# Sheet_C1.net
KiCad netlist of a schematic drawn in Altium Designer
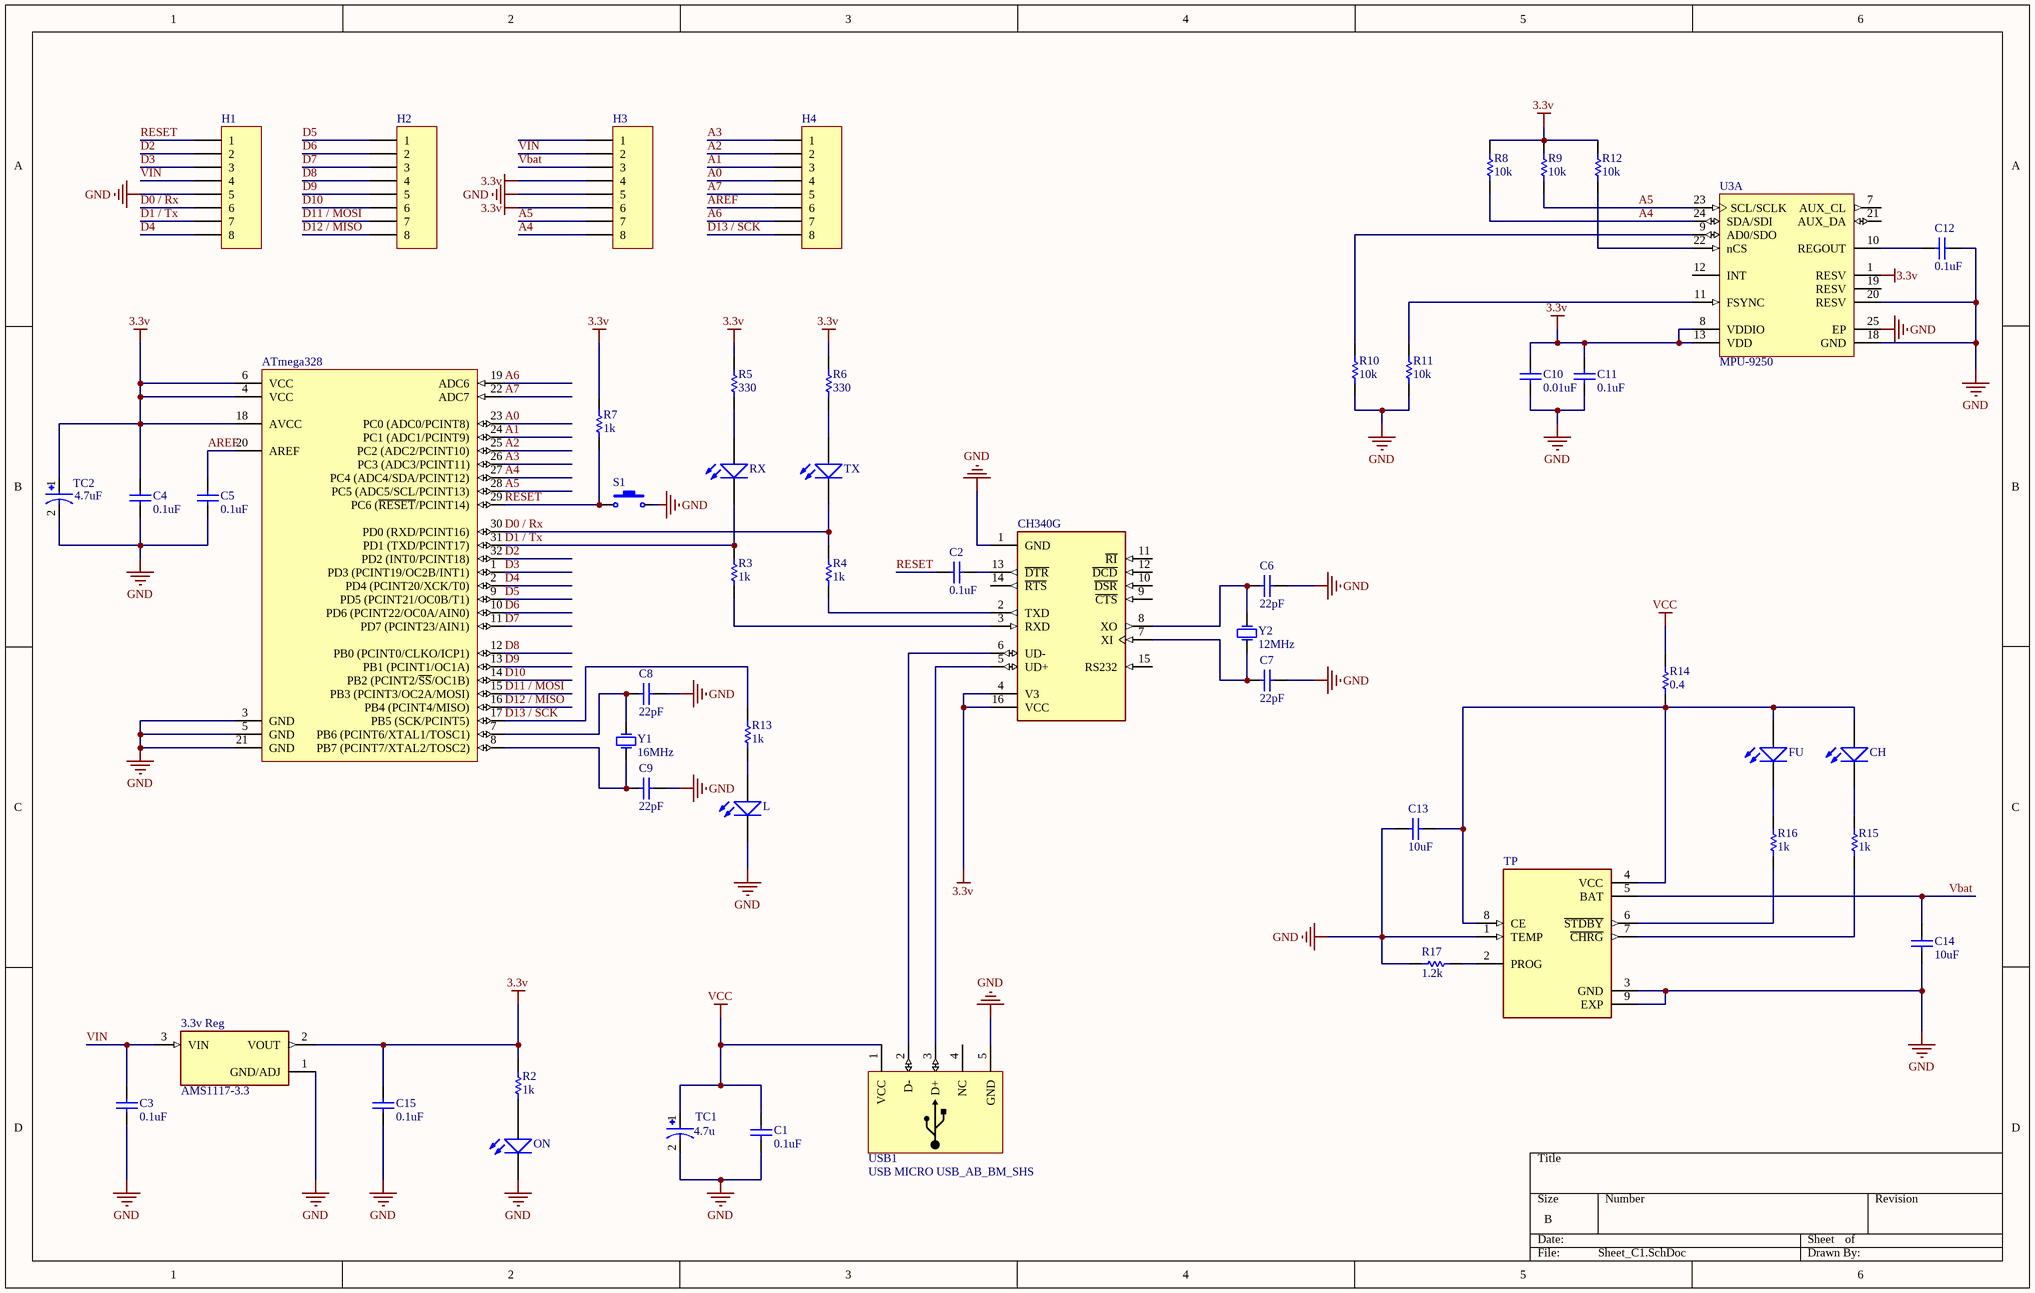
[diagram p0: Sheet_C1.SchDoc]

(export (version "E")
  (design (tool "Eeschema 10.0.6"))
  (components
    (comp (ref "3.3v Reg")
      (value "AMS1117-3.3")
      (footprint "SOT229P700X180-4N")
      (description "Sot223/Pkg 1-Amp 3.3-Volt Low Drop Out Voltage Regulatator")
      (fields (field (name "MF") "Advanced Monolithic Systems"))
      (libsource (lib "AMS1117-3.3") (part "AMS1117-3.3"))
    )
    (comp (ref "ATmega328")
      (value "~")
      (footprint "32A_L")
      (libsource (lib "Altium Content Vault") (part "MC-8B-ATM48-SQ32"))
    )
    (comp (ref "C1")
      (value "0.1uF")
      (footprint "CAP0805")
      (description "CAP0805")
      (libsource (lib "CAP0805") (part "CAP0805"))
    )
    (comp (ref "C2")
      (value "0.1uF")
      (footprint "CAP0805")
      (description "CAP0805")
      (libsource (lib "CAP0805") (part "CAP0805"))
    )
    (comp (ref "C3")
      (value "0.1uF")
      (footprint "CAP0805")
      (description "CAP0805")
      (libsource (lib "CAP0805") (part "CAP0805"))
    )
    (comp (ref "C4")
      (value "0.1uF")
      (footprint "CAP0805")
      (description "CAP0805")
      (libsource (lib "CAP0805") (part "CAP0805"))
    )
    (comp (ref "C5")
      (value "0.1uF")
      (footprint "CAP0805")
      (description "CAP0805")
      (libsource (lib "CAP0805") (part "CAP0805"))
    )
    (comp (ref "C6")
      (value "22pF")
      (footprint "CAP0805")
      (description "CAP0805")
      (libsource (lib "CAP0805") (part "CAP0805"))
    )
    (comp (ref "C7")
      (value "22pF")
      (footprint "CAP0805")
      (description "CAP0805")
      (libsource (lib "CAP0805") (part "CAP0805"))
    )
    (comp (ref "C8")
      (value "22pF")
      (footprint "CAP0805")
      (description "CAP0805")
      (libsource (lib "CAP0805") (part "CAP0805"))
    )
    (comp (ref "C9")
      (value "22pF")
      (footprint "CAP0805")
      (description "CAP0805")
      (libsource (lib "CAP0805") (part "CAP0805"))
    )
    (comp (ref "C10")
      (value "0.01uF")
      (footprint "CAP0805")
      (description "CAP0805")
      (libsource (lib "CAP0805") (part "CAP0805"))
    )
    (comp (ref "C11")
      (value "0.1uF")
      (footprint "CAP0805")
      (description "CAP0805")
      (libsource (lib "CAP0805") (part "CAP0805"))
    )
    (comp (ref "C12")
      (value "0.1uF")
      (footprint "CAP0805")
      (description "CAP0805")
      (libsource (lib "CAP0805") (part "CAP0805"))
    )
    (comp (ref "C13")
      (value "10uF")
      (footprint "CAP0805")
      (description "CAP0805")
      (libsource (lib "CAP0805") (part "CAP0805"))
    )
    (comp (ref "C14")
      (value "10uF")
      (footprint "CAP0805")
      (description "CAP0805")
      (libsource (lib "CAP0805") (part "CAP0805"))
    )
    (comp (ref "C15")
      (value "0.1uF")
      (footprint "CAP0805")
      (description "CAP0805")
      (libsource (lib "CAP0805") (part "CAP0805"))
    )
    (comp (ref "CH")
      (value "~")
      (footprint "LED_SMD_0805")
      (libsource (lib "LED_SMD_0805") (part "LED_SMD_0805"))
    )
    (comp (ref "CH340G")
      (value "~")
      (footprint "SOIC127P600X180-16N")
      (description "USB Interface Integrated Circuit")
      (fields (field (name "MP") "Ch340G") (field (name "MF") "WCH"))
      (libsource (lib "CH340G") (part "CH340G"))
    )
    (comp (ref "FU")
      (value "~")
      (footprint "LED_SMD_0805")
      (libsource (lib "LED_SMD_0805") (part "LED_SMD_0805"))
    )
    (comp (ref "H1") (value "~") (footprint "Header 8") (libsource (lib "Header 8") (part "Header 8")))
    (comp (ref "H2") (value "~") (footprint "Header 8") (libsource (lib "Header 8") (part "Header 8")))
    (comp (ref "H3") (value "~") (footprint "Header 8") (libsource (lib "Header 8") (part "Header 8")))
    (comp (ref "H4") (value "~") (footprint "Header 8") (libsource (lib "Header 8") (part "Header 8")))
    (comp (ref "L")
      (value "~")
      (footprint "LED_SMD_0805")
      (libsource (lib "LED_SMD_0805") (part "LED_SMD_0805"))
    )
    (comp (ref "ON")
      (value "~")
      (footprint "LED_SMD_0805")
      (libsource (lib "LED_SMD_0805") (part "LED_SMD_0805"))
    )
    (comp (ref "R2")
      (value "1k")
      (footprint "RES0805")
      (description "RES0805")
      (libsource (lib "RES0805") (part "RES0805"))
    )
    (comp (ref "R3")
      (value "1k")
      (footprint "RES0805")
      (description "RES0805")
      (libsource (lib "RES0805") (part "RES0805"))
    )
    (comp (ref "R4")
      (value "1k")
      (footprint "RES0805")
      (description "RES0805")
      (libsource (lib "RES0805") (part "RES0805"))
    )
    (comp (ref "R5")
      (value "330")
      (footprint "RES0805")
      (description "RES0805")
      (libsource (lib "RES0805") (part "RES0805"))
    )
    (comp (ref "R6")
      (value "330")
      (footprint "RES0805")
      (description "RES0805")
      (libsource (lib "RES0805") (part "RES0805"))
    )
    (comp (ref "R7")
      (value "1k")
      (footprint "RES0805")
      (description "RES0805")
      (libsource (lib "RES0805") (part "RES0805"))
    )
    (comp (ref "R8")
      (value "10k")
      (footprint "RES0805")
      (description "RES0805")
      (libsource (lib "RES0805") (part "RES0805"))
    )
    (comp (ref "R9")
      (value "10k")
      (footprint "RES0805")
      (description "RES0805")
      (libsource (lib "RES0805") (part "RES0805"))
    )
    (comp (ref "R10")
      (value "10k")
      (footprint "RES0805")
      (description "RES0805")
      (libsource (lib "RES0805") (part "RES0805"))
    )
    (comp (ref "R11")
      (value "10k")
      (footprint "RES0805")
      (description "RES0805")
      (libsource (lib "RES0805") (part "RES0805"))
    )
    (comp (ref "R12")
      (value "10k")
      (footprint "RES0805")
      (description "RES0805")
      (libsource (lib "RES0805") (part "RES0805"))
    )
    (comp (ref "R13")
      (value "1k")
      (footprint "RES0805")
      (description "RES0805")
      (libsource (lib "RES0805") (part "RES0805"))
    )
    (comp (ref "R14")
      (value "0.4")
      (footprint "RES0805")
      (description "RES0805")
      (libsource (lib "RES0805") (part "RES0805"))
    )
    (comp (ref "R15")
      (value "1k")
      (footprint "RES0805")
      (description "RES0805")
      (libsource (lib "RES0805") (part "RES0805"))
    )
    (comp (ref "R16")
      (value "1k")
      (footprint "RES0805")
      (description "RES0805")
      (libsource (lib "RES0805") (part "RES0805"))
    )
    (comp (ref "R17")
      (value "1.2k")
      (footprint "RES0805")
      (description "RES0805")
      (libsource (lib "RES0805") (part "RES0805"))
    )
    (comp (ref "RX")
      (value "~")
      (footprint "LED_SMD_0805")
      (libsource (lib "LED_SMD_0805") (part "LED_SMD_0805"))
    )
    (comp (ref "S1")
      (value "~")
      (footprint "Push Button Switch SMD")
      (libsource (lib "Push Button Switch SMD") (part "Push Button Switch SMD"))
    )
    (comp (ref "TC1")
      (value "4.7u")
      (footprint "CAPMP3516X190N")
      (description "4.7 ÂµF Molded Tantalum Capacitors 25 V 1411 (3528 Metric), 1210 1.5Ohm")
      (fields (field (name "MP") "TAJB475K025RNJ") (field (name "MF") "AVX"))
      (libsource (lib "TAJB475K025RNJ") (part "TAJB475K025RNJ"))
    )
    (comp (ref "TC2")
      (value "4.7uF")
      (footprint "CAPMP3516X190N")
      (description "4.7 ÂµF Molded Tantalum Capacitors 25 V 1411 (3528 Metric), 1210 1.5Ohm")
      (fields (field (name "MP") "TAJB475K025RNJ") (field (name "MF") "AVX"))
      (libsource (lib "TAJB475K025RNJ") (part "TAJB475K025RNJ"))
    )
    (comp (ref "TP")
      (value "~")
      (footprint "SOIC127P600X175-9N")
      (description "TP4056-42-ESOP8 TP")
      (fields (field (name "MF") "Lite-On Semiconductor") (field (name "MP") "TP4056-42-ESOP8"))
      (libsource (lib "TP4056-42-ESOP8") (part "TP4056-42-ESOP8"))
    )
    (comp (ref "TX")
      (value "~")
      (footprint "LED_SMD_0805")
      (libsource (lib "LED_SMD_0805") (part "LED_SMD_0805"))
    )
    (comp (ref "U3")
      (value "MPU-9250")
      (footprint "INSE-QFN-24-1700X1540TP_M")
      (description "9-axis MotionTracking device, 2.4 to 3,6 V, -40 to 85 degC, 24-Pin QFN, RoHS, Tape and Reel")
      (fields (field (name "MANUFACTURER") "InvenSense"))
      (libsource (lib "Altium Content Vault") (part "INSE-MPU-9250-QFN-24"))
    )
    (comp (ref "USB1")
      (value "USB MICRO USB_AB_BM_SHS")
      (footprint "USB MICRO USB_AB_BM_SHS")
      (libsource (lib "USB MICRO USB_AB_BM_SHS") (part "USB MICRO USB_AB_BM_SHS"))
    )
    (comp (ref "Y1")
      (value "16MHz")
      (footprint "Crystal SMD")
      (description "Crystal SMD")
      (libsource (lib "Crystal SMD") (part "Crystal SMD"))
    )
    (comp (ref "Y2")
      (value "12MHz")
      (footprint "Crystal SMD")
      (description "Crystal SMD")
      (libsource (lib "Crystal SMD") (part "Crystal SMD"))
    )
  )
  (nets
    (net (code "1") (name "/A0") (class "Default")
      (node (ref "ATmega328") (pin "23") (pinfunction "PC0_(ADC0/PCINT8)_23") (pintype "bidirectional"))
      (node (ref "H4") (pin "4") (pinfunction "4_4") (pintype "passive"))
    )
    (net (code "2") (name "/A1") (class "Default")
      (node (ref "ATmega328") (pin "24") (pinfunction "PC1_(ADC1/PCINT9)_24") (pintype "bidirectional"))
      (node (ref "H4") (pin "3") (pinfunction "3_3") (pintype "passive"))
    )
    (net (code "3") (name "/A2") (class "Default")
      (node (ref "ATmega328") (pin "25") (pinfunction "PC2_(ADC2/PCINT10)_25") (pintype "bidirectional"))
      (node (ref "H4") (pin "2") (pinfunction "2_2") (pintype "passive"))
    )
    (net (code "4") (name "/A3") (class "Default")
      (node (ref "ATmega328") (pin "26") (pinfunction "PC3_(ADC3/PCINT11)_26") (pintype "bidirectional"))
      (node (ref "H4") (pin "1") (pinfunction "1_1") (pintype "passive"))
    )
    (net (code "5") (name "/A4") (class "Default")
      (node (ref "ATmega328") (pin "27") (pinfunction "PC4_(ADC4/SDA/PCINT12)_27") (pintype "bidirectional"))
      (node (ref "H3") (pin "8") (pinfunction "8_8") (pintype "passive"))
      (node (ref "R8") (pin "1") (pinfunction "1_1") (pintype "passive"))
      (node (ref "U3") (pin "24") (pinfunction "SDA/SDI_24") (pintype "bidirectional"))
    )
    (net (code "6") (name "/A5") (class "Default")
      (node (ref "ATmega328") (pin "28") (pinfunction "PC5_(ADC5/SCL/PCINT13)_28") (pintype "bidirectional"))
      (node (ref "H3") (pin "7") (pinfunction "7_7") (pintype "passive"))
      (node (ref "R9") (pin "1") (pinfunction "1_1") (pintype "passive"))
      (node (ref "U3") (pin "23") (pinfunction "SCL/SCLK_23") (pintype "input"))
    )
    (net (code "7") (name "/A6") (class "Default")
      (node (ref "ATmega328") (pin "19") (pinfunction "ADC6_19") (pintype "input"))
      (node (ref "H4") (pin "7") (pinfunction "7_7") (pintype "passive"))
    )
    (net (code "8") (name "/A7") (class "Default")
      (node (ref "ATmega328") (pin "22") (pinfunction "ADC7_22") (pintype "input"))
      (node (ref "H4") (pin "5") (pinfunction "5_5") (pintype "passive"))
    )
    (net (code "9") (name "/AREF") (class "Default")
      (node (ref "ATmega328") (pin "20") (pinfunction "AREF_20") (pintype "passive"))
      (node (ref "C5") (pin "2") (pinfunction "2_2") (pintype "passive"))
      (node (ref "H4") (pin "6") (pinfunction "6_6") (pintype "passive"))
    )
    (net (code "10") (name "/D0 {slash} Rx") (class "Default")
      (node (ref "ATmega328") (pin "30") (pinfunction "PD0_(RXD/PCINT16)_30") (pintype "bidirectional"))
      (node (ref "H1") (pin "6") (pinfunction "6_6") (pintype "passive"))
      (node (ref "R4") (pin "2") (pinfunction "2_2") (pintype "passive"))
      (node (ref "TX") (pin "1") (pinfunction "K_1") (pintype "passive"))
    )
    (net (code "11") (name "/D1 {slash} Tx") (class "Default")
      (node (ref "ATmega328") (pin "31") (pinfunction "PD1_(TXD/PCINT17)_31") (pintype "bidirectional"))
      (node (ref "H1") (pin "7") (pinfunction "7_7") (pintype "passive"))
      (node (ref "R3") (pin "2") (pinfunction "2_2") (pintype "passive"))
      (node (ref "RX") (pin "1") (pinfunction "K_1") (pintype "passive"))
    )
    (net (code "12") (name "/D2") (class "Default")
      (node (ref "ATmega328") (pin "32") (pinfunction "PD2_(INT0/PCINT18)_32") (pintype "bidirectional"))
      (node (ref "H1") (pin "2") (pinfunction "2_2") (pintype "passive"))
    )
    (net (code "13") (name "/D3") (class "Default")
      (node (ref "ATmega328") (pin "1") (pinfunction "PD3_(PCINT19/OC2B/INT1)_1") (pintype "bidirectional"))
      (node (ref "H1") (pin "3") (pinfunction "3_3") (pintype "passive"))
    )
    (net (code "14") (name "/D4") (class "Default")
      (node (ref "ATmega328") (pin "2") (pinfunction "PD4_(PCINT20/XCK/T0)_2") (pintype "bidirectional"))
      (node (ref "H1") (pin "8") (pinfunction "8_8") (pintype "passive"))
    )
    (net (code "15") (name "/D5") (class "Default")
      (node (ref "ATmega328") (pin "9") (pinfunction "PD5_(PCINT21/OC0B/T1)_9") (pintype "bidirectional"))
      (node (ref "H2") (pin "1") (pinfunction "1_1") (pintype "passive"))
    )
    (net (code "16") (name "/D6") (class "Default")
      (node (ref "ATmega328") (pin "10") (pinfunction "PD6_(PCINT22/OC0A/AIN0)_10") (pintype "bidirectional"))
      (node (ref "H2") (pin "2") (pinfunction "2_2") (pintype "passive"))
    )
    (net (code "17") (name "/D7") (class "Default")
      (node (ref "ATmega328") (pin "11") (pinfunction "PD7_(PCINT23/AIN1)_11") (pintype "bidirectional"))
      (node (ref "H2") (pin "3") (pinfunction "3_3") (pintype "passive"))
    )
    (net (code "18") (name "/D8") (class "Default")
      (node (ref "ATmega328") (pin "12") (pinfunction "PB0_(PCINT0/CLKO/ICP1)_12") (pintype "bidirectional"))
      (node (ref "H2") (pin "4") (pinfunction "4_4") (pintype "passive"))
    )
    (net (code "19") (name "/D9") (class "Default")
      (node (ref "ATmega328") (pin "13") (pinfunction "PB1_(PCINT1/OC1A)_13") (pintype "bidirectional"))
      (node (ref "H2") (pin "5") (pinfunction "5_5") (pintype "passive"))
    )
    (net (code "20") (name "/D10") (class "Default")
      (node (ref "ATmega328") (pin "14") (pinfunction "PB2_(PCINT2/~{SS}/OC1B)_14") (pintype "bidirectional"))
      (node (ref "H2") (pin "6") (pinfunction "6_6") (pintype "passive"))
    )
    (net (code "21") (name "/D11 {slash} MOSI") (class "Default")
      (node (ref "ATmega328") (pin "15") (pinfunction "PB3_(PCINT3/OC2A/MOSI)_15") (pintype "bidirectional"))
      (node (ref "H2") (pin "7") (pinfunction "7_7") (pintype "passive"))
    )
    (net (code "22") (name "/D12 {slash} MISO") (class "Default")
      (node (ref "ATmega328") (pin "16") (pinfunction "PB4_(PCINT4/MISO)_16") (pintype "bidirectional"))
      (node (ref "H2") (pin "8") (pinfunction "8_8") (pintype "passive"))
    )
    (net (code "23") (name "/D13 {slash} SCK") (class "Default")
      (node (ref "ATmega328") (pin "17") (pinfunction "PB5_(SCK/PCINT5)_17") (pintype "bidirectional"))
      (node (ref "H4") (pin "8") (pinfunction "8_8") (pintype "passive"))
      (node (ref "R13") (pin "1") (pinfunction "1_1") (pintype "passive"))
    )
    (net (code "24") (name "/RESET") (class "Default")
      (node (ref "ATmega328") (pin "29") (pinfunction "PC6_(~{RESET}/PCINT14)_29") (pintype "bidirectional"))
      (node (ref "C2") (pin "2") (pinfunction "2_2") (pintype "passive"))
      (node (ref "H1") (pin "1") (pinfunction "1_1") (pintype "passive"))
      (node (ref "R7") (pin "1") (pinfunction "1_1") (pintype "passive"))
      (node (ref "S1") (pin "1") (pinfunction "1_1") (pintype "passive"))
    )
    (net (code "25") (name "/VIN") (class "Default")
      (node (ref "3.3v Reg") (pin "3") (pinfunction "VIN_3") (pintype "input"))
      (node (ref "C3") (pin "1") (pinfunction "1_1") (pintype "passive"))
      (node (ref "H1") (pin "4") (pinfunction "4_4") (pintype "passive"))
      (node (ref "H3") (pin "2") (pinfunction "2_2") (pintype "passive"))
    )
    (net (code "26") (name "/Vbat") (class "Default")
      (node (ref "C14") (pin "2") (pinfunction "2_2") (pintype "passive"))
      (node (ref "H3") (pin "3") (pinfunction "3_3") (pintype "passive"))
      (node (ref "TP") (pin "5") (pinfunction "BAT_5") (pintype "power_in"))
    )
    (net (code "27") (name "3.3v") (class "Default")
      (node (ref "3.3v Reg") (pin "2") (pinfunction "VOUT_2") (pintype "output"))
      (node (ref "ATmega328") (pin "18") (pinfunction "AVCC_18") (pintype "power_in"))
      (node (ref "ATmega328") (pin "4") (pinfunction "VCC_4") (pintype "power_in"))
      (node (ref "ATmega328") (pin "6") (pinfunction "VCC_6") (pintype "power_in"))
      (node (ref "C10") (pin "2") (pinfunction "2_2") (pintype "passive"))
      (node (ref "C11") (pin "2") (pinfunction "2_2") (pintype "passive"))
      (node (ref "C15") (pin "2") (pinfunction "2_2") (pintype "passive"))
      (node (ref "C4") (pin "1") (pinfunction "1_1") (pintype "passive"))
      (node (ref "CH340G") (pin "16") (pinfunction "VCC_16") (pintype "power_in"))
      (node (ref "CH340G") (pin "4") (pinfunction "V3_4") (pintype "power_in"))
      (node (ref "H3") (pin "4") (pinfunction "4_4") (pintype "passive"))
      (node (ref "H3") (pin "6") (pinfunction "6_6") (pintype "passive"))
      (node (ref "R12") (pin "2") (pinfunction "2_2") (pintype "passive"))
      (node (ref "R2") (pin "2") (pinfunction "2_2") (pintype "passive"))
      (node (ref "R5") (pin "2") (pinfunction "2_2") (pintype "passive"))
      (node (ref "R6") (pin "2") (pinfunction "2_2") (pintype "passive"))
      (node (ref "R7") (pin "2") (pinfunction "2_2") (pintype "passive"))
      (node (ref "R8") (pin "2") (pinfunction "2_2") (pintype "passive"))
      (node (ref "R9") (pin "2") (pinfunction "2_2") (pintype "passive"))
      (node (ref "TC2") (pin "1") (pinfunction "1_1") (pintype "passive"))
      (node (ref "U3") (pin "1") (pinfunction "RESV_1") (pintype "power_in"))
      (node (ref "U3") (pin "13") (pinfunction "VDD_13") (pintype "power_in"))
      (node (ref "U3") (pin "8") (pinfunction "VDDIO_8") (pintype "power_in"))
    )
    (net (code "28") (name "GND") (class "Default")
      (node (ref "3.3v Reg") (pin "1") (pinfunction "GND/ADJ_1") (pintype "power_in"))
      (node (ref "ATmega328") (pin "21") (pinfunction "GND_21") (pintype "power_in"))
      (node (ref "ATmega328") (pin "3") (pinfunction "GND_3") (pintype "power_in"))
      (node (ref "ATmega328") (pin "5") (pinfunction "GND_5") (pintype "power_in"))
      (node (ref "C1") (pin "1") (pinfunction "1_1") (pintype "passive"))
      (node (ref "C10") (pin "1") (pinfunction "1_1") (pintype "passive"))
      (node (ref "C11") (pin "1") (pinfunction "1_1") (pintype "passive"))
      (node (ref "C12") (pin "2") (pinfunction "2_2") (pintype "passive"))
      (node (ref "C13") (pin "2") (pinfunction "2_2") (pintype "passive"))
      (node (ref "C14") (pin "1") (pinfunction "1_1") (pintype "passive"))
      (node (ref "C15") (pin "1") (pinfunction "1_1") (pintype "passive"))
      (node (ref "C3") (pin "2") (pinfunction "2_2") (pintype "passive"))
      (node (ref "C4") (pin "2") (pinfunction "2_2") (pintype "passive"))
      (node (ref "C5") (pin "1") (pinfunction "1_1") (pintype "passive"))
      (node (ref "C6") (pin "1") (pinfunction "1_1") (pintype "passive"))
      (node (ref "C7") (pin "1") (pinfunction "1_1") (pintype "passive"))
      (node (ref "C8") (pin "1") (pinfunction "1_1") (pintype "passive"))
      (node (ref "C9") (pin "1") (pinfunction "1_1") (pintype "passive"))
      (node (ref "CH340G") (pin "1") (pinfunction "GND_1") (pintype "power_in"))
      (node (ref "H1") (pin "5") (pinfunction "5_5") (pintype "passive"))
      (node (ref "H3") (pin "5") (pinfunction "5_5") (pintype "passive"))
      (node (ref "L") (pin "1") (pinfunction "K_1") (pintype "passive"))
      (node (ref "ON") (pin "1") (pinfunction "K_1") (pintype "passive"))
      (node (ref "R10") (pin "2") (pinfunction "2_2") (pintype "passive"))
      (node (ref "R11") (pin "1") (pinfunction "1_1") (pintype "passive"))
      (node (ref "R17") (pin "1") (pinfunction "1_1") (pintype "passive"))
      (node (ref "S1") (pin "2") (pinfunction "2_2") (pintype "passive"))
      (node (ref "TC1") (pin "2") (pinfunction "2_2") (pintype "passive"))
      (node (ref "TC2") (pin "2") (pinfunction "2_2") (pintype "passive"))
      (node (ref "TP") (pin "1") (pinfunction "TEMP_1") (pintype "input"))
      (node (ref "TP") (pin "3") (pinfunction "GND_3") (pintype "power_in"))
      (node (ref "TP") (pin "9") (pinfunction "EXP_9") (pintype "passive"))
      (node (ref "U3") (pin "18") (pinfunction "GND_18") (pintype "power_in"))
      (node (ref "U3") (pin "20") (pinfunction "RESV_20") (pintype "power_in"))
      (node (ref "U3") (pin "25") (pinfunction "EP_25") (pintype "passive"))
      (node (ref "USB1") (pin "5") (pinfunction "GND_5") (pintype "power_in"))
    )
    (net (code "29") (name "Net-(ATmega328-PB6_(PCINT6{slash}XTAL1{slash}TOSC1))") (class "Default")
      (node (ref "ATmega328") (pin "7") (pinfunction "PB6_(PCINT6/XTAL1/TOSC1)_7") (pintype "bidirectional"))
      (node (ref "C8") (pin "2") (pinfunction "2_2") (pintype "passive"))
      (node (ref "Y1") (pin "2") (pinfunction "OSC2_2") (pintype "passive"))
    )
    (net (code "30") (name "Net-(ATmega328-PB7_(PCINT7{slash}XTAL2{slash}TOSC2))") (class "Default")
      (node (ref "ATmega328") (pin "8") (pinfunction "PB7_(PCINT7/XTAL2/TOSC2)_8") (pintype "bidirectional"))
      (node (ref "C9") (pin "2") (pinfunction "2_2") (pintype "passive"))
      (node (ref "Y1") (pin "1") (pinfunction "OSC1_1") (pintype "passive"))
    )
    (net (code "31") (name "Net-(CH-A)") (class "Default")
      (node (ref "C13") (pin "1") (pinfunction "1_1") (pintype "passive"))
      (node (ref "CH") (pin "2") (pinfunction "A_2") (pintype "passive"))
      (node (ref "FU") (pin "2") (pinfunction "A_2") (pintype "passive"))
      (node (ref "R14") (pin "1") (pinfunction "1_1") (pintype "passive"))
      (node (ref "TP") (pin "4") (pinfunction "VCC_4") (pintype "power_in"))
      (node (ref "TP") (pin "8") (pinfunction "CE_8") (pintype "input"))
    )
    (net (code "32") (name "Net-(CH-K)") (class "Default")
      (node (ref "CH") (pin "1") (pinfunction "K_1") (pintype "passive"))
      (node (ref "R15") (pin "1") (pinfunction "1_1") (pintype "passive"))
    )
    (net (code "33") (name "Net-(CH340G-RXD)") (class "Default")
      (node (ref "CH340G") (pin "3") (pinfunction "RXD_3") (pintype "input"))
      (node (ref "R3") (pin "1") (pinfunction "1_1") (pintype "passive"))
    )
    (net (code "34") (name "Net-(CH340G-TXD)") (class "Default")
      (node (ref "CH340G") (pin "2") (pinfunction "TXD_2") (pintype "output"))
      (node (ref "R4") (pin "1") (pinfunction "1_1") (pintype "passive"))
    )
    (net (code "35") (name "Net-(CH340G-UD+)") (class "Default")
      (node (ref "CH340G") (pin "5") (pinfunction "UD+_5") (pintype "bidirectional"))
      (node (ref "USB1") (pin "3") (pinfunction "D+_3") (pintype "bidirectional"))
    )
    (net (code "36") (name "Net-(CH340G-UD-)") (class "Default")
      (node (ref "CH340G") (pin "6") (pinfunction "UD-_6") (pintype "bidirectional"))
      (node (ref "USB1") (pin "2") (pinfunction "D-_2") (pintype "bidirectional"))
    )
    (net (code "37") (name "Net-(CH340G-XI)") (class "Default")
      (node (ref "C7") (pin "2") (pinfunction "2_2") (pintype "passive"))
      (node (ref "CH340G") (pin "7") (pinfunction "XI_7") (pintype "input"))
      (node (ref "Y2") (pin "1") (pinfunction "OSC1_1") (pintype "passive"))
    )
    (net (code "38") (name "Net-(CH340G-XO)") (class "Default")
      (node (ref "C6") (pin "2") (pinfunction "2_2") (pintype "passive"))
      (node (ref "CH340G") (pin "8") (pinfunction "XO_8") (pintype "output"))
      (node (ref "Y2") (pin "2") (pinfunction "OSC2_2") (pintype "passive"))
    )
    (net (code "39") (name "Net-(CH340G-~{DTR})") (class "Default")
      (node (ref "C2") (pin "1") (pinfunction "1_1") (pintype "passive"))
      (node (ref "CH340G") (pin "13") (pinfunction "~{DTR}_13") (pintype "output"))
    )
    (net (code "40") (name "Net-(FU-K)") (class "Default")
      (node (ref "FU") (pin "1") (pinfunction "K_1") (pintype "passive"))
      (node (ref "R16") (pin "2") (pinfunction "2_2") (pintype "passive"))
    )
    (net (code "41") (name "Net-(L-A)") (class "Default")
      (node (ref "L") (pin "2") (pinfunction "A_2") (pintype "passive"))
      (node (ref "R13") (pin "2") (pinfunction "2_2") (pintype "passive"))
    )
    (net (code "42") (name "Net-(ON-A)") (class "Default")
      (node (ref "ON") (pin "2") (pinfunction "A_2") (pintype "passive"))
      (node (ref "R2") (pin "1") (pinfunction "1_1") (pintype "passive"))
    )
    (net (code "43") (name "Net-(RX-A)") (class "Default")
      (node (ref "R5") (pin "1") (pinfunction "1_1") (pintype "passive"))
      (node (ref "RX") (pin "2") (pinfunction "A_2") (pintype "passive"))
    )
    (net (code "44") (name "Net-(TP-PROG)") (class "Default")
      (node (ref "R17") (pin "2") (pinfunction "2_2") (pintype "passive"))
      (node (ref "TP") (pin "2") (pinfunction "PROG_2") (pintype "passive"))
    )
    (net (code "45") (name "Net-(TP-~{CHRG})") (class "Default")
      (node (ref "R15") (pin "2") (pinfunction "2_2") (pintype "passive"))
      (node (ref "TP") (pin "7") (pinfunction "~{CHRG}_7") (pintype "output"))
    )
    (net (code "46") (name "Net-(TP-~{STDBY})") (class "Default")
      (node (ref "R16") (pin "1") (pinfunction "1_1") (pintype "passive"))
      (node (ref "TP") (pin "6") (pinfunction "~{STDBY}_6") (pintype "output"))
    )
    (net (code "47") (name "Net-(TX-A)") (class "Default")
      (node (ref "R6") (pin "1") (pinfunction "1_1") (pintype "passive"))
      (node (ref "TX") (pin "2") (pinfunction "A_2") (pintype "passive"))
    )
    (net (code "48") (name "Net-(U3A-AD0{slash}SDO)") (class "Default")
      (node (ref "R10") (pin "1") (pinfunction "1_1") (pintype "passive"))
      (node (ref "U3") (pin "9") (pinfunction "AD0/SDO_9") (pintype "bidirectional"))
    )
    (net (code "49") (name "Net-(U3A-FSYNC)") (class "Default")
      (node (ref "R11") (pin "2") (pinfunction "2_2") (pintype "passive"))
      (node (ref "U3") (pin "11") (pinfunction "FSYNC_11") (pintype "input"))
    )
    (net (code "50") (name "Net-(U3A-REGOUT)") (class "Default")
      (node (ref "C12") (pin "1") (pinfunction "1_1") (pintype "passive"))
      (node (ref "U3") (pin "10") (pinfunction "REGOUT_10") (pintype "passive"))
    )
    (net (code "51") (name "Net-(U3A-nCS)") (class "Default")
      (node (ref "R12") (pin "1") (pinfunction "1_1") (pintype "passive"))
      (node (ref "U3") (pin "22") (pinfunction "nCS_22") (pintype "input"))
    )
    (net (code "52") (name "VCC") (class "Default")
      (node (ref "C1") (pin "2") (pinfunction "2_2") (pintype "passive"))
      (node (ref "R14") (pin "2") (pinfunction "2_2") (pintype "passive"))
      (node (ref "TC1") (pin "1") (pinfunction "1_1") (pintype "passive"))
      (node (ref "USB1") (pin "1") (pinfunction "VCC_1") (pintype "power_in"))
    )
    (net (code "53") (name "unconnected-(CH340G-RS232-Pad15)") (class "Default")
      (node (ref "CH340G") (pin "15") (pinfunction "RS232_15") (pintype "input"))
    )
    (net (code "54") (name "unconnected-(CH340G-~{CTS}-Pad9)") (class "Default")
      (node (ref "CH340G") (pin "9") (pinfunction "~{CTS}_9") (pintype "input"))
    )
    (net (code "55") (name "unconnected-(CH340G-~{DCD}-Pad12)") (class "Default")
      (node (ref "CH340G") (pin "12") (pinfunction "~{DCD}_12") (pintype "input"))
    )
    (net (code "56") (name "unconnected-(CH340G-~{DSR}-Pad10)") (class "Default")
      (node (ref "CH340G") (pin "10") (pinfunction "~{DSR}_10") (pintype "input"))
    )
    (net (code "57") (name "unconnected-(CH340G-~{RI}-Pad11)") (class "Default")
      (node (ref "CH340G") (pin "11") (pinfunction "~{RI}_11") (pintype "input"))
    )
    (net (code "58") (name "unconnected-(CH340G-~{RTS}-Pad14)") (class "Default")
      (node (ref "CH340G") (pin "14") (pinfunction "~{RTS}_14") (pintype "output"))
    )
    (net (code "59") (name "unconnected-(H3-Pad1)") (class "Default")
      (node (ref "H3") (pin "1") (pinfunction "1_1") (pintype "passive"))
    )
    (net (code "60") (name "unconnected-(U3A-AUX_CL-Pad7)") (class "Default")
      (node (ref "U3") (pin "7") (pinfunction "AUX_CL_7") (pintype "output"))
    )
    (net (code "61") (name "unconnected-(U3A-AUX_DA-Pad21)") (class "Default")
      (node (ref "U3") (pin "21") (pinfunction "AUX_DA_21") (pintype "bidirectional"))
    )
    (net (code "62") (name "unconnected-(U3A-INT-Pad12)") (class "Default")
      (node (ref "U3") (pin "12") (pinfunction "INT_12") (pintype "tri_state"))
    )
    (net (code "63") (name "unconnected-(U3A-RESV-Pad19)") (class "Default")
      (node (ref "U3") (pin "19") (pinfunction "RESV_19") (pintype "passive"))
    )
    (net (code "64") (name "unconnected-(USB1-NC-Pad4)") (class "Default")
      (node (ref "USB1") (pin "4") (pinfunction "NC_4") (pintype "passive"))
    )
  )
)
